# G2-PMS.net
KiCad netlist of a schematic drawn in Altium Designer
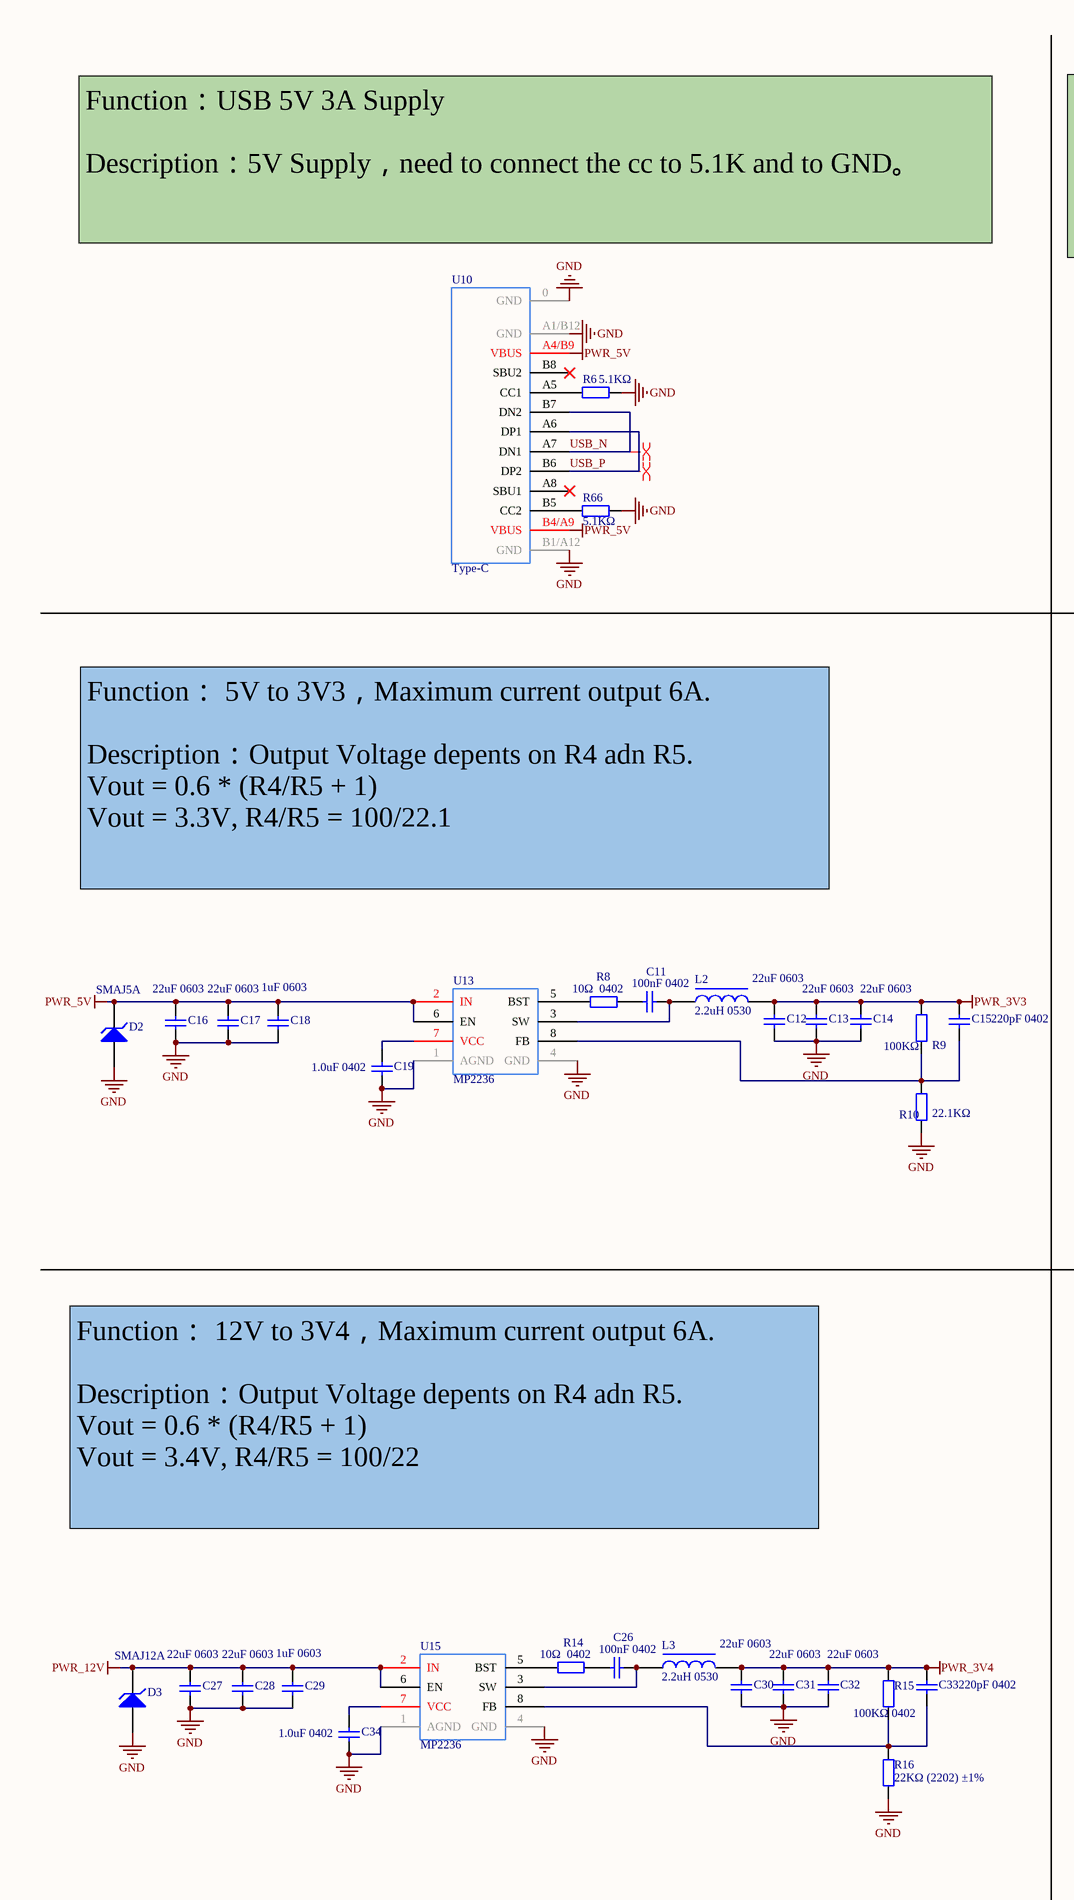
[diagram p0: G2-PMS.SchDoc, left]
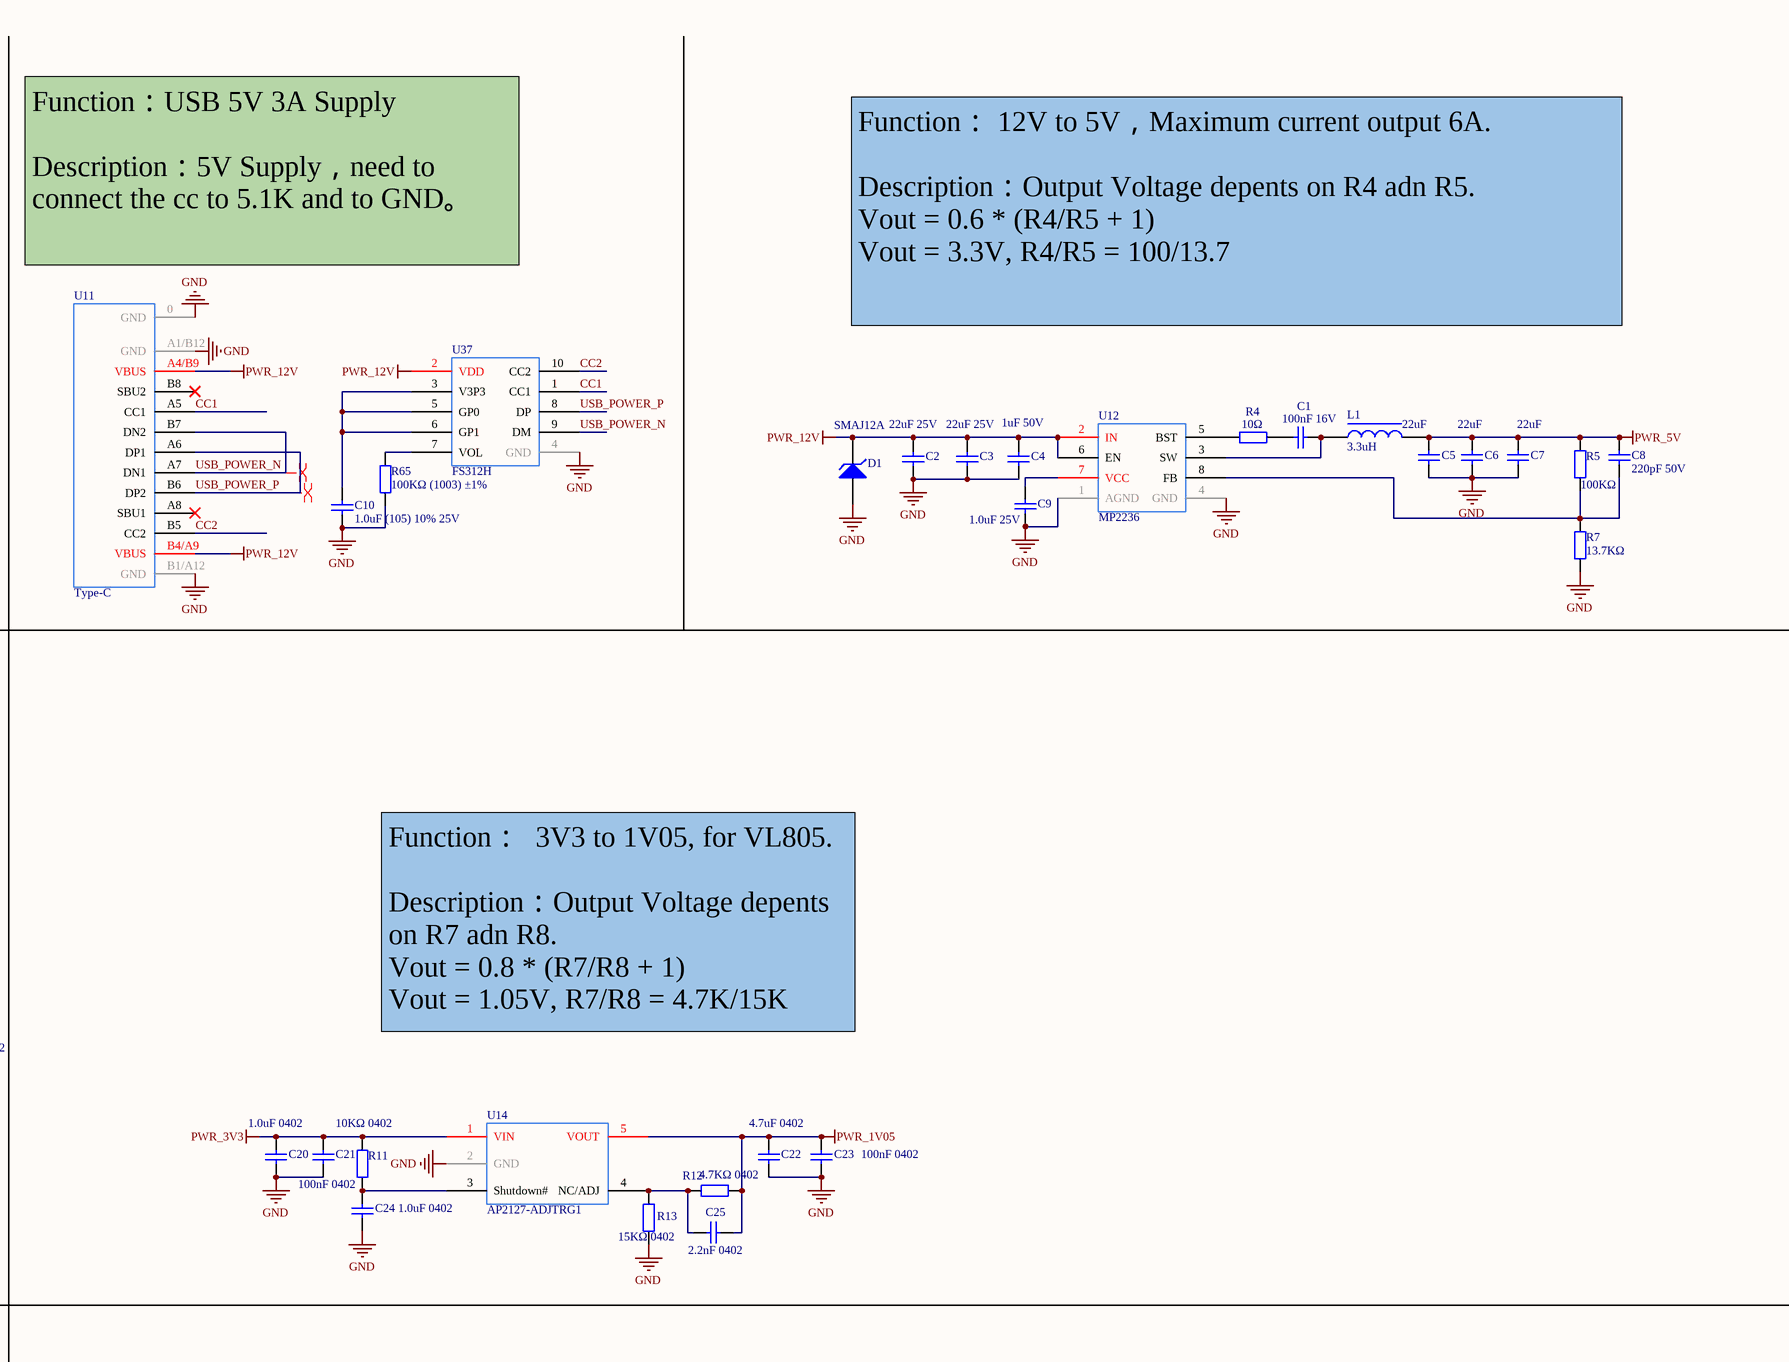
[diagram p1: G2-PMS.SchDoc, right]

(export (version "E")
  (design (tool "Eeschema 10.0.6"))
  (components
    (comp (ref "C1")
      (value "100nF 16V")
      (footprint "0402_C")
      (description "贴片电容")
      (libsource (lib "Miscellaneous Devices LC") (part "0402 100nF (104) 10% 16V"))
    )
    (comp (ref "C2")
      (value "22uF 25V")
      (footprint "0805_C")
      (description "贴片电容")
      (libsource (lib "Miscellaneous Devices LC") (part "0805 22uF (226) 20% 25V"))
    )
    (comp (ref "C3")
      (value "22uF 25V")
      (footprint "0805_C")
      (description "贴片电容")
      (libsource (lib "Miscellaneous Devices LC") (part "0805 22uF (226) 20% 25V"))
    )
    (comp (ref "C4")
      (value "1uF 50V")
      (footprint "0805_C")
      (description "贴片电容")
      (libsource (lib "Miscellaneous Devices LC") (part "0805 1uF (105) 10% 50V"))
    )
    (comp (ref "C5")
      (value "22uF")
      (footprint "0805_C")
      (description "贴片电容")
      (libsource (lib "Miscellaneous Devices LC") (part "0805 22uF (226) 20% 25V"))
    )
    (comp (ref "C6")
      (value "22uF")
      (footprint "0805_C")
      (description "贴片电容")
      (libsource (lib "Miscellaneous Devices LC") (part "0805 22uF (226) 20% 25V"))
    )
    (comp (ref "C7")
      (value "22uF")
      (footprint "0805_C")
      (description "贴片电容")
      (libsource (lib "Miscellaneous Devices LC") (part "0805 22uF (226) 20% 25V"))
    )
    (comp (ref "C8")
      (value "220pF 50V")
      (footprint "0402_C")
      (description "贴片电容")
      (libsource (lib "Miscellaneous Devices LC") (part "0402 220pF (221) 10% 50V"))
    )
    (comp (ref "C9")
      (value "1.0uF 25V")
      (footprint "0402_C")
      (description "贴片电容")
      (libsource (lib "Miscellaneous Devices LC") (part "0402 1.0uF (105) 10% 25V"))
    )
    (comp (ref "C10")
      (value "1.0uF (105) 10% 25V")
      (footprint "0402_C")
      (description "贴片电容")
      (libsource (lib "Miscellaneous Devices LC") (part "0402 1.0uF (105) 10% 25V"))
    )
    (comp (ref "C11")
      (value "100nF 0402")
      (footprint "0402_C")
      (description "贴片电容")
      (libsource (lib "Miscellaneous Devices LC") (part "0402 100nF (104) 10% 16V"))
    )
    (comp (ref "C12")
      (value "22uF 0603")
      (footprint "0603_C")
      (description "贴片电容")
      (libsource (lib "Miscellaneous Devices LC") (part "0603 22uF (226) 20% 6.3V"))
    )
    (comp (ref "C13")
      (value "22uF 0603")
      (footprint "0603_C")
      (description "贴片电容")
      (libsource (lib "Miscellaneous Devices LC") (part "0603 22uF (226) 20% 6.3V"))
    )
    (comp (ref "C14")
      (value "22uF 0603")
      (footprint "0603_C")
      (description "贴片电容")
      (libsource (lib "Miscellaneous Devices LC") (part "0603 22uF (226) 20% 6.3V"))
    )
    (comp (ref "C15")
      (value "220pF 0402")
      (footprint "0402_C")
      (description "贴片电容")
      (libsource (lib "Miscellaneous Devices LC") (part "0402 220pF (221) 10% 50V"))
    )
    (comp (ref "C16")
      (value "22uF 0603")
      (footprint "0603_C")
      (description "贴片电容")
      (libsource (lib "Miscellaneous Devices LC") (part "0603 22uF (226) 20% 6.3V"))
    )
    (comp (ref "C17")
      (value "22uF 0603")
      (footprint "0603_C")
      (description "贴片电容")
      (libsource (lib "Miscellaneous Devices LC") (part "0603 22uF (226) 20% 6.3V"))
    )
    (comp (ref "C18")
      (value "1uF 0603")
      (footprint "0603_C")
      (description "贴片电容")
      (libsource (lib "Miscellaneous Devices LC") (part "0603 1uF (105) 10% 50V"))
    )
    (comp (ref "C19")
      (value "1.0uF 0402")
      (footprint "0402_C")
      (description "贴片电容")
      (libsource (lib "Miscellaneous Devices LC") (part "0402 1.0uF (105) 10% 25V"))
    )
    (comp (ref "C20")
      (value "1.0uF 0402")
      (footprint "0402_C")
      (description "贴片电容")
      (libsource (lib "Miscellaneous Devices LC") (part "0402 1.0uF (105) 10% 25V"))
    )
    (comp (ref "C21")
      (value "100nF 0402")
      (footprint "0402_C")
      (description "贴片电容")
      (libsource (lib "Miscellaneous Devices LC") (part "0402 100nF (104) 10% 16V"))
    )
    (comp (ref "C22")
      (value "4.7uF 0402")
      (footprint "0402_C")
      (description "贴片电容")
      (libsource (lib "Miscellaneous Devices LC") (part "0402 4.7uF (475) 20% 10V"))
    )
    (comp (ref "C23")
      (value "100nF 0402")
      (footprint "0402_C")
      (description "贴片电容")
      (libsource (lib "Miscellaneous Devices LC") (part "0402 100nF (104) 10% 16V"))
    )
    (comp (ref "C24")
      (value "1.0uF 0402")
      (footprint "0402_C")
      (description "贴片电容")
      (libsource (lib "Miscellaneous Devices LC") (part "0402 1.0uF (105) 10% 25V"))
    )
    (comp (ref "C25")
      (value "2.2nF 0402")
      (footprint "0402_C")
      (description "贴片电容")
      (libsource (lib "Miscellaneous Devices LC") (part "0402 2.2nF (222) 10% 50V"))
    )
    (comp (ref "C26")
      (value "100nF 0402")
      (footprint "0402_C")
      (description "贴片电容")
      (libsource (lib "Miscellaneous Devices LC") (part "0402 100nF (104) 10% 16V"))
    )
    (comp (ref "C27")
      (value "22uF 0603")
      (footprint "0603_C")
      (description "贴片电容")
      (libsource (lib "Miscellaneous Devices LC") (part "0603 22uF (226) 20% 6.3V"))
    )
    (comp (ref "C28")
      (value "22uF 0603")
      (footprint "0603_C")
      (description "贴片电容")
      (libsource (lib "Miscellaneous Devices LC") (part "0603 22uF (226) 20% 6.3V"))
    )
    (comp (ref "C29")
      (value "1uF 0603")
      (footprint "0603_C")
      (description "贴片电容")
      (libsource (lib "Miscellaneous Devices LC") (part "0603 1uF (105) 10% 50V"))
    )
    (comp (ref "C30")
      (value "22uF 0603")
      (footprint "0603_C")
      (description "贴片电容")
      (libsource (lib "Miscellaneous Devices LC") (part "0603 22uF (226) 20% 6.3V"))
    )
    (comp (ref "C31")
      (value "22uF 0603")
      (footprint "0603_C")
      (description "贴片电容")
      (libsource (lib "Miscellaneous Devices LC") (part "0603 22uF (226) 20% 6.3V"))
    )
    (comp (ref "C32")
      (value "22uF 0603")
      (footprint "0603_C")
      (description "贴片电容")
      (libsource (lib "Miscellaneous Devices LC") (part "0603 22uF (226) 20% 6.3V"))
    )
    (comp (ref "C33")
      (value "220pF 0402")
      (footprint "0402_C")
      (description "贴片电容")
      (libsource (lib "Miscellaneous Devices LC") (part "0402 220pF (221) 10% 50V"))
    )
    (comp (ref "C34")
      (value "1.0uF 0402")
      (footprint "0402_C")
      (description "贴片电容")
      (libsource (lib "Miscellaneous Devices LC") (part "0402 1.0uF (105) 10% 25V"))
    )
    (comp (ref "D1")
      (value "SMAJ12A")
      (footprint "SMAJ12A")
      (description "TVS")
      (libsource (lib "Mars") (part "SMAJ12A"))
    )
    (comp (ref "D2")
      (value "SMAJ5A")
      (footprint "SMAJ12A")
      (description "TVS")
      (libsource (lib "Mars") (part "SMAJ12A"))
    )
    (comp (ref "D3")
      (value "SMAJ12A")
      (footprint "SMAJ12A")
      (description "TVS")
      (libsource (lib "Mars") (part "SMAJ12A"))
    )
    (comp (ref "L1")
      (value "3.3uH")
      (footprint "0530")
      (description "3.3uH 0630")
      (libsource (lib "Mars") (part "3.3uH"))
    )
    (comp (ref "L2")
      (value "2.2uH 0530")
      (footprint "0530")
      (description "2.2uH 0630")
      (libsource (lib "Mars") (part "2.2uH"))
    )
    (comp (ref "L3")
      (value "2.2uH 0530")
      (footprint "0530")
      (description "2.2uH 0630")
      (libsource (lib "Mars") (part "2.2uH"))
    )
    (comp (ref "R4")
      (value "10Ω")
      (footprint "0402_R")
      (description "贴片电阻")
      (libsource (lib "Miscellaneous Devices LC") (part "0402 10Ω (10R0) 1%"))
    )
    (comp (ref "R5")
      (value "100KΩ")
      (footprint "0402_R")
      (description "贴片电阻")
      (libsource (lib "Miscellaneous Devices LC") (part "0402 100KΩ (1003) 1%"))
    )
    (comp (ref "R6")
      (value "5.1KΩ")
      (footprint "0402_R")
      (description "贴片电阻")
      (libsource (lib "Miscellaneous Devices LC") (part "0402 5.1KΩ (5101) 1%"))
    )
    (comp (ref "R7")
      (value "13.7KΩ")
      (footprint "0402_R")
      (description "贴片电阻")
      (libsource (lib "Miscellaneous Devices LC") (part "0402 10KΩ (1002) 1%"))
    )
    (comp (ref "R8")
      (value "10Ω  0402")
      (footprint "0402_R")
      (description "贴片电阻")
      (libsource (lib "Miscellaneous Devices LC") (part "0402 10Ω (10R0) 1%"))
    )
    (comp (ref "R9")
      (value "100KΩ")
      (footprint "0402_R")
      (description "贴片电阻")
      (libsource (lib "Miscellaneous Devices LC") (part "0402 100KΩ (1003) 1%"))
    )
    (comp (ref "R10")
      (value "22.1KΩ")
      (footprint "0402_R")
      (description "贴片电阻")
      (libsource (lib "Miscellaneous Devices LC") (part "0402 10KΩ (1002) 1%"))
    )
    (comp (ref "R11")
      (value "10KΩ 0402")
      (footprint "0402_R")
      (description "贴片电阻")
      (libsource (lib "Miscellaneous Devices LC") (part "0402 10KΩ (1002) 1%"))
    )
    (comp (ref "R12")
      (value "4.7KΩ 0402")
      (footprint "0402_R")
      (description "贴片电阻")
      (libsource (lib "Miscellaneous Devices LC") (part "0402 4.7KΩ (4701) 1%"))
    )
    (comp (ref "R13")
      (value "15KΩ 0402")
      (footprint "0402_R")
      (description "贴片电阻")
      (libsource (lib "Miscellaneous Devices LC") (part "0402 15KΩ (1502) 1%"))
    )
    (comp (ref "R14")
      (value "10Ω  0402")
      (footprint "0402_R")
      (description "贴片电阻")
      (libsource (lib "Miscellaneous Devices LC") (part "0402 10Ω (10R0) 1%"))
    )
    (comp (ref "R15")
      (value "100KΩ 0402")
      (footprint "0402_R")
      (description "贴片电阻")
      (libsource (lib "Miscellaneous Devices LC") (part "0402 100KΩ (1003) 1%"))
    )
    (comp (ref "R16")
      (value "22KΩ (2202) ±1%")
      (footprint "0402_R")
      (description "贴片电阻")
      (libsource (lib "Miscellaneous Devices LC") (part "0402 22KΩ (2202) 1%"))
    )
    (comp (ref "R65")
      (value "100KΩ (1003) ±1%")
      (footprint "0402_R")
      (description "贴片电阻")
      (libsource (lib "Miscellaneous Devices LC") (part "0402 100KΩ (1003) 1%"))
    )
    (comp (ref "R66")
      (value "5.1KΩ")
      (footprint "0402_R")
      (description "贴片电阻")
      (libsource (lib "Miscellaneous Devices LC") (part "0402 5.1KΩ (5101) 1%"))
    )
    (comp (ref "U10")
      (value "Type-C")
      (footprint "Type-C-16P")
      (description "Type-C-16P")
      (libsource (lib "Mars") (part "Type-C-16P"))
    )
    (comp (ref "U11")
      (value "Type-C")
      (footprint "Type-C-16P")
      (description "Type-C-16P")
      (libsource (lib "Mars") (part "Type-C-16P"))
    )
    (comp (ref "U12")
      (value "MP2236")
      (footprint "MP2236")
      (description "Vin=18, Iout=6A")
      (libsource (lib "Mars") (part "MP2236"))
    )
    (comp (ref "U13")
      (value "MP2236")
      (footprint "MP2236")
      (description "Vin=18, Iout=6A")
      (libsource (lib "Mars") (part "MP2236"))
    )
    (comp (ref "U14")
      (value "AP2127-ADJTRG1")
      (footprint "AP2127K")
      (description "3.3V-1.05V")
      (libsource (lib "Mars") (part "AP2127-ADJTRG1"))
    )
    (comp (ref "U15")
      (value "MP2236")
      (footprint "MP2236")
      (description "Vin=18, Iout=6A")
      (libsource (lib "Mars") (part "MP2236"))
    )
    (comp (ref "U37")
      (value "FS312H")
      (footprint "FS312H")
      (description "USB POWER PD 20V")
      (libsource (lib "Mars") (part "FS312H"))
    )
  )
  (nets
    (net (code "1") (name "/CC1") (class "Default")
      (node (ref "U11") (pin "A5") (pinfunction "CC1_A5") (pintype "passive"))
      (node (ref "U37") (pin "1") (pinfunction "CC1_1") (pintype "passive"))
    )
    (net (code "2") (name "/CC2") (class "Default")
      (node (ref "U11") (pin "B5") (pinfunction "CC2_B5") (pintype "passive"))
      (node (ref "U37") (pin "10") (pinfunction "CC2_10") (pintype "passive"))
    )
    (net (code "3") (name "/USB_N") (class "Default")
      (node (ref "U10") (pin "A7") (pinfunction "DN1_A7") (pintype "passive"))
      (node (ref "U10") (pin "B7") (pinfunction "DN2_B7") (pintype "passive"))
    )
    (net (code "4") (name "/USB_P") (class "Default")
      (node (ref "U10") (pin "A6") (pinfunction "DP1_A6") (pintype "passive"))
      (node (ref "U10") (pin "B6") (pinfunction "DP2_B6") (pintype "passive"))
    )
    (net (code "5") (name "/USB_POWER_N") (class "Default")
      (node (ref "U11") (pin "A7") (pinfunction "DN1_A7") (pintype "passive"))
      (node (ref "U11") (pin "B7") (pinfunction "DN2_B7") (pintype "passive"))
      (node (ref "U37") (pin "9") (pinfunction "DM_9") (pintype "passive"))
    )
    (net (code "6") (name "/USB_POWER_P") (class "Default")
      (node (ref "U11") (pin "A6") (pinfunction "DP1_A6") (pintype "passive"))
      (node (ref "U11") (pin "B6") (pinfunction "DP2_B6") (pintype "passive"))
      (node (ref "U37") (pin "8") (pinfunction "DP_8") (pintype "passive"))
    )
    (net (code "7") (name "GND") (class "Default")
      (node (ref "C10") (pin "1") (pinfunction "1_1") (pintype "passive"))
      (node (ref "C12") (pin "1") (pinfunction "1_1") (pintype "passive"))
      (node (ref "C13") (pin "1") (pinfunction "1_1") (pintype "passive"))
      (node (ref "C14") (pin "1") (pinfunction "1_1") (pintype "passive"))
      (node (ref "C16") (pin "1") (pinfunction "1_1") (pintype "passive"))
      (node (ref "C17") (pin "1") (pinfunction "1_1") (pintype "passive"))
      (node (ref "C18") (pin "1") (pinfunction "1_1") (pintype "passive"))
      (node (ref "C19") (pin "1") (pinfunction "1_1") (pintype "passive"))
      (node (ref "C2") (pin "1") (pinfunction "1_1") (pintype "passive"))
      (node (ref "C20") (pin "1") (pinfunction "1_1") (pintype "passive"))
      (node (ref "C21") (pin "1") (pinfunction "1_1") (pintype "passive"))
      (node (ref "C22") (pin "1") (pinfunction "1_1") (pintype "passive"))
      (node (ref "C23") (pin "1") (pinfunction "1_1") (pintype "passive"))
      (node (ref "C24") (pin "1") (pinfunction "1_1") (pintype "passive"))
      (node (ref "C27") (pin "1") (pinfunction "1_1") (pintype "passive"))
      (node (ref "C28") (pin "1") (pinfunction "1_1") (pintype "passive"))
      (node (ref "C29") (pin "1") (pinfunction "1_1") (pintype "passive"))
      (node (ref "C3") (pin "1") (pinfunction "1_1") (pintype "passive"))
      (node (ref "C30") (pin "1") (pinfunction "1_1") (pintype "passive"))
      (node (ref "C31") (pin "1") (pinfunction "1_1") (pintype "passive"))
      (node (ref "C32") (pin "1") (pinfunction "1_1") (pintype "passive"))
      (node (ref "C34") (pin "1") (pinfunction "1_1") (pintype "passive"))
      (node (ref "C4") (pin "1") (pinfunction "1_1") (pintype "passive"))
      (node (ref "C5") (pin "1") (pinfunction "1_1") (pintype "passive"))
      (node (ref "C6") (pin "1") (pinfunction "1_1") (pintype "passive"))
      (node (ref "C7") (pin "1") (pinfunction "1_1") (pintype "passive"))
      (node (ref "C9") (pin "1") (pinfunction "1_1") (pintype "passive"))
      (node (ref "D1") (pin "1") (pinfunction "A_1") (pintype "passive"))
      (node (ref "D2") (pin "1") (pinfunction "A_1") (pintype "passive"))
      (node (ref "D3") (pin "1") (pinfunction "A_1") (pintype "passive"))
      (node (ref "R10") (pin "1") (pinfunction "1_1") (pintype "passive"))
      (node (ref "R13") (pin "1") (pinfunction "1_1") (pintype "passive"))
      (node (ref "R16") (pin "1") (pinfunction "1_1") (pintype "passive"))
      (node (ref "R6") (pin "2") (pinfunction "2_2") (pintype "passive"))
      (node (ref "R65") (pin "1") (pinfunction "1_1") (pintype "passive"))
      (node (ref "R66") (pin "2") (pinfunction "2_2") (pintype "passive"))
      (node (ref "R7") (pin "1") (pinfunction "1_1") (pintype "passive"))
      (node (ref "U10") (pin "0") (pinfunction "GND_0") (pintype "passive"))
      (node (ref "U10") (pin "A1/B12") (pinfunction "GND_A1/B12") (pintype "passive"))
      (node (ref "U10") (pin "B1/A12") (pinfunction "GND_B1/A12") (pintype "passive"))
      (node (ref "U11") (pin "0") (pinfunction "GND_0") (pintype "passive"))
      (node (ref "U11") (pin "A1/B12") (pinfunction "GND_A1/B12") (pintype "passive"))
      (node (ref "U11") (pin "B1/A12") (pinfunction "GND_B1/A12") (pintype "passive"))
      (node (ref "U12") (pin "1") (pinfunction "AGND_1") (pintype "passive"))
      (node (ref "U12") (pin "4") (pinfunction "GND_4") (pintype "passive"))
      (node (ref "U13") (pin "1") (pinfunction "AGND_1") (pintype "passive"))
      (node (ref "U13") (pin "4") (pinfunction "GND_4") (pintype "passive"))
      (node (ref "U14") (pin "2") (pinfunction "GND_2") (pintype "passive"))
      (node (ref "U15") (pin "1") (pinfunction "AGND_1") (pintype "passive"))
      (node (ref "U15") (pin "4") (pinfunction "GND_4") (pintype "passive"))
      (node (ref "U37") (pin "4") (pinfunction "GND_4") (pintype "passive"))
    )
    (net (code "8") (name "Net-(C1-Pad1)") (class "Default")
      (node (ref "C1") (pin "1") (pinfunction "1_1") (pintype "passive"))
      (node (ref "R4") (pin "2") (pinfunction "2_2") (pintype "passive"))
    )
    (net (code "9") (name "Net-(C11-Pad1)") (class "Default")
      (node (ref "C11") (pin "1") (pinfunction "1_1") (pintype "passive"))
      (node (ref "R8") (pin "2") (pinfunction "2_2") (pintype "passive"))
    )
    (net (code "10") (name "Net-(C26-Pad1)") (class "Default")
      (node (ref "C26") (pin "1") (pinfunction "1_1") (pintype "passive"))
      (node (ref "R14") (pin "2") (pinfunction "2_2") (pintype "passive"))
    )
    (net (code "11") (name "Net-(U10-CC1)") (class "Default")
      (node (ref "R6") (pin "1") (pinfunction "1_1") (pintype "passive"))
      (node (ref "U10") (pin "A5") (pinfunction "CC1_A5") (pintype "passive"))
    )
    (net (code "12") (name "Net-(U10-CC2)") (class "Default")
      (node (ref "R66") (pin "1") (pinfunction "1_1") (pintype "passive"))
      (node (ref "U10") (pin "B5") (pinfunction "CC2_B5") (pintype "passive"))
    )
    (net (code "13") (name "Net-(U12-BST)") (class "Default")
      (node (ref "R4") (pin "1") (pinfunction "1_1") (pintype "passive"))
      (node (ref "U12") (pin "5") (pinfunction "BST_5") (pintype "passive"))
    )
    (net (code "14") (name "Net-(U12-FB)") (class "Default")
      (node (ref "C8") (pin "1") (pinfunction "1_1") (pintype "passive"))
      (node (ref "R5") (pin "1") (pinfunction "1_1") (pintype "passive"))
      (node (ref "R7") (pin "2") (pinfunction "2_2") (pintype "passive"))
      (node (ref "U12") (pin "8") (pinfunction "FB_8") (pintype "passive"))
    )
    (net (code "15") (name "Net-(U12-SW)") (class "Default")
      (node (ref "C1") (pin "2") (pinfunction "2_2") (pintype "passive"))
      (node (ref "L1") (pin "1") (pinfunction "1_1") (pintype "passive"))
      (node (ref "U12") (pin "3") (pinfunction "SW_3") (pintype "passive"))
    )
    (net (code "16") (name "Net-(U12-VCC)") (class "Default")
      (node (ref "C9") (pin "2") (pinfunction "2_2") (pintype "passive"))
      (node (ref "U12") (pin "7") (pinfunction "VCC_7") (pintype "passive"))
    )
    (net (code "17") (name "Net-(U13-BST)") (class "Default")
      (node (ref "R8") (pin "1") (pinfunction "1_1") (pintype "passive"))
      (node (ref "U13") (pin "5") (pinfunction "BST_5") (pintype "passive"))
    )
    (net (code "18") (name "Net-(U13-FB)") (class "Default")
      (node (ref "C15") (pin "1") (pinfunction "1_1") (pintype "passive"))
      (node (ref "R10") (pin "2") (pinfunction "2_2") (pintype "passive"))
      (node (ref "R9") (pin "1") (pinfunction "1_1") (pintype "passive"))
      (node (ref "U13") (pin "8") (pinfunction "FB_8") (pintype "passive"))
    )
    (net (code "19") (name "Net-(U13-SW)") (class "Default")
      (node (ref "C11") (pin "2") (pinfunction "2_2") (pintype "passive"))
      (node (ref "L2") (pin "1") (pinfunction "1_1") (pintype "passive"))
      (node (ref "U13") (pin "3") (pinfunction "SW_3") (pintype "passive"))
    )
    (net (code "20") (name "Net-(U13-VCC)") (class "Default")
      (node (ref "C19") (pin "2") (pinfunction "2_2") (pintype "passive"))
      (node (ref "U13") (pin "7") (pinfunction "VCC_7") (pintype "passive"))
    )
    (net (code "21") (name "Net-(U14-NC{slash}ADJ)") (class "Default")
      (node (ref "C25") (pin "1") (pinfunction "1_1") (pintype "passive"))
      (node (ref "R12") (pin "1") (pinfunction "1_1") (pintype "passive"))
      (node (ref "R13") (pin "2") (pinfunction "2_2") (pintype "passive"))
      (node (ref "U14") (pin "4") (pinfunction "NC/ADJ_4") (pintype "passive"))
    )
    (net (code "22") (name "Net-(U14-Shutdown#)") (class "Default")
      (node (ref "C24") (pin "2") (pinfunction "2_2") (pintype "passive"))
      (node (ref "R11") (pin "1") (pinfunction "1_1") (pintype "passive"))
      (node (ref "U14") (pin "3") (pinfunction "Shutdown#_3") (pintype "passive"))
    )
    (net (code "23") (name "Net-(U15-BST)") (class "Default")
      (node (ref "R14") (pin "1") (pinfunction "1_1") (pintype "passive"))
      (node (ref "U15") (pin "5") (pinfunction "BST_5") (pintype "passive"))
    )
    (net (code "24") (name "Net-(U15-FB)") (class "Default")
      (node (ref "C33") (pin "1") (pinfunction "1_1") (pintype "passive"))
      (node (ref "R15") (pin "1") (pinfunction "1_1") (pintype "passive"))
      (node (ref "R16") (pin "2") (pinfunction "2_2") (pintype "passive"))
      (node (ref "U15") (pin "8") (pinfunction "FB_8") (pintype "passive"))
    )
    (net (code "25") (name "Net-(U15-SW)") (class "Default")
      (node (ref "C26") (pin "2") (pinfunction "2_2") (pintype "passive"))
      (node (ref "L3") (pin "1") (pinfunction "1_1") (pintype "passive"))
      (node (ref "U15") (pin "3") (pinfunction "SW_3") (pintype "passive"))
    )
    (net (code "26") (name "Net-(U15-VCC)") (class "Default")
      (node (ref "C34") (pin "2") (pinfunction "2_2") (pintype "passive"))
      (node (ref "U15") (pin "7") (pinfunction "VCC_7") (pintype "passive"))
    )
    (net (code "27") (name "Net-(U37-GP0)") (class "Default")
      (node (ref "C10") (pin "2") (pinfunction "2_2") (pintype "passive"))
      (node (ref "U37") (pin "3") (pinfunction "V3P3_3") (pintype "passive"))
      (node (ref "U37") (pin "5") (pinfunction "GP0_5") (pintype "passive"))
      (node (ref "U37") (pin "6") (pinfunction "GP1_6") (pintype "passive"))
    )
    (net (code "28") (name "Net-(U37-VOL)") (class "Default")
      (node (ref "R65") (pin "2") (pinfunction "2_2") (pintype "passive"))
      (node (ref "U37") (pin "7") (pinfunction "VOL_7") (pintype "passive"))
    )
    (net (code "29") (name "PWR_1V05") (class "Default")
      (node (ref "C22") (pin "2") (pinfunction "2_2") (pintype "passive"))
      (node (ref "C23") (pin "2") (pinfunction "2_2") (pintype "passive"))
      (node (ref "C25") (pin "2") (pinfunction "2_2") (pintype "passive"))
      (node (ref "R12") (pin "2") (pinfunction "2_2") (pintype "passive"))
      (node (ref "U14") (pin "5") (pinfunction "VOUT_5") (pintype "passive"))
    )
    (net (code "30") (name "PWR_3V3") (class "Default")
      (node (ref "C12") (pin "2") (pinfunction "2_2") (pintype "passive"))
      (node (ref "C13") (pin "2") (pinfunction "2_2") (pintype "passive"))
      (node (ref "C14") (pin "2") (pinfunction "2_2") (pintype "passive"))
      (node (ref "C15") (pin "2") (pinfunction "2_2") (pintype "passive"))
      (node (ref "C20") (pin "2") (pinfunction "2_2") (pintype "passive"))
      (node (ref "C21") (pin "2") (pinfunction "2_2") (pintype "passive"))
      (node (ref "L2") (pin "2") (pinfunction "2_2") (pintype "passive"))
      (node (ref "R11") (pin "2") (pinfunction "2_2") (pintype "passive"))
      (node (ref "R9") (pin "2") (pinfunction "2_2") (pintype "passive"))
      (node (ref "U14") (pin "1") (pinfunction "VIN_1") (pintype "passive"))
    )
    (net (code "31") (name "PWR_3V4") (class "Default")
      (node (ref "C30") (pin "2") (pinfunction "2_2") (pintype "passive"))
      (node (ref "C31") (pin "2") (pinfunction "2_2") (pintype "passive"))
      (node (ref "C32") (pin "2") (pinfunction "2_2") (pintype "passive"))
      (node (ref "C33") (pin "2") (pinfunction "2_2") (pintype "passive"))
      (node (ref "L3") (pin "2") (pinfunction "2_2") (pintype "passive"))
      (node (ref "R15") (pin "2") (pinfunction "2_2") (pintype "passive"))
    )
    (net (code "32") (name "PWR_5V") (class "Default")
      (node (ref "C16") (pin "2") (pinfunction "2_2") (pintype "passive"))
      (node (ref "C17") (pin "2") (pinfunction "2_2") (pintype "passive"))
      (node (ref "C18") (pin "2") (pinfunction "2_2") (pintype "passive"))
      (node (ref "C5") (pin "2") (pinfunction "2_2") (pintype "passive"))
      (node (ref "C6") (pin "2") (pinfunction "2_2") (pintype "passive"))
      (node (ref "C7") (pin "2") (pinfunction "2_2") (pintype "passive"))
      (node (ref "C8") (pin "2") (pinfunction "2_2") (pintype "passive"))
      (node (ref "D2") (pin "2") (pinfunction "C_2") (pintype "passive"))
      (node (ref "L1") (pin "2") (pinfunction "2_2") (pintype "passive"))
      (node (ref "R5") (pin "2") (pinfunction "2_2") (pintype "passive"))
      (node (ref "U10") (pin "A4/B9") (pinfunction "VBUS_A4/B9") (pintype "passive"))
      (node (ref "U10") (pin "B4/A9") (pinfunction "VBUS_B4/A9") (pintype "passive"))
      (node (ref "U13") (pin "2") (pinfunction "IN_2") (pintype "passive"))
      (node (ref "U13") (pin "6") (pinfunction "EN_6") (pintype "passive"))
    )
    (net (code "33") (name "PWR_12V") (class "Default")
      (node (ref "C2") (pin "2") (pinfunction "2_2") (pintype "passive"))
      (node (ref "C27") (pin "2") (pinfunction "2_2") (pintype "passive"))
      (node (ref "C28") (pin "2") (pinfunction "2_2") (pintype "passive"))
      (node (ref "C29") (pin "2") (pinfunction "2_2") (pintype "passive"))
      (node (ref "C3") (pin "2") (pinfunction "2_2") (pintype "passive"))
      (node (ref "C4") (pin "2") (pinfunction "2_2") (pintype "passive"))
      (node (ref "D1") (pin "2") (pinfunction "C_2") (pintype "passive"))
      (node (ref "D3") (pin "2") (pinfunction "C_2") (pintype "passive"))
      (node (ref "U11") (pin "A4/B9") (pinfunction "VBUS_A4/B9") (pintype "passive"))
      (node (ref "U11") (pin "B4/A9") (pinfunction "VBUS_B4/A9") (pintype "passive"))
      (node (ref "U12") (pin "2") (pinfunction "IN_2") (pintype "passive"))
      (node (ref "U12") (pin "6") (pinfunction "EN_6") (pintype "passive"))
      (node (ref "U15") (pin "2") (pinfunction "IN_2") (pintype "passive"))
      (node (ref "U15") (pin "6") (pinfunction "EN_6") (pintype "passive"))
      (node (ref "U37") (pin "2") (pinfunction "VDD_2") (pintype "passive"))
    )
    (net (code "34") (name "unconnected-(U10-SBU1-PadA8)") (class "Default")
      (node (ref "U10") (pin "A8") (pinfunction "SBU1_A8") (pintype "passive+no_connect"))
    )
    (net (code "35") (name "unconnected-(U10-SBU2-PadB8)") (class "Default")
      (node (ref "U10") (pin "B8") (pinfunction "SBU2_B8") (pintype "passive+no_connect"))
    )
    (net (code "36") (name "unconnected-(U11-SBU1-PadA8)") (class "Default")
      (node (ref "U11") (pin "A8") (pinfunction "SBU1_A8") (pintype "passive+no_connect"))
    )
    (net (code "37") (name "unconnected-(U11-SBU2-PadB8)") (class "Default")
      (node (ref "U11") (pin "B8") (pinfunction "SBU2_B8") (pintype "passive+no_connect"))
    )
  )
)
